# schematic.net
KiCad netlist of a schematic drawn in EAGLE
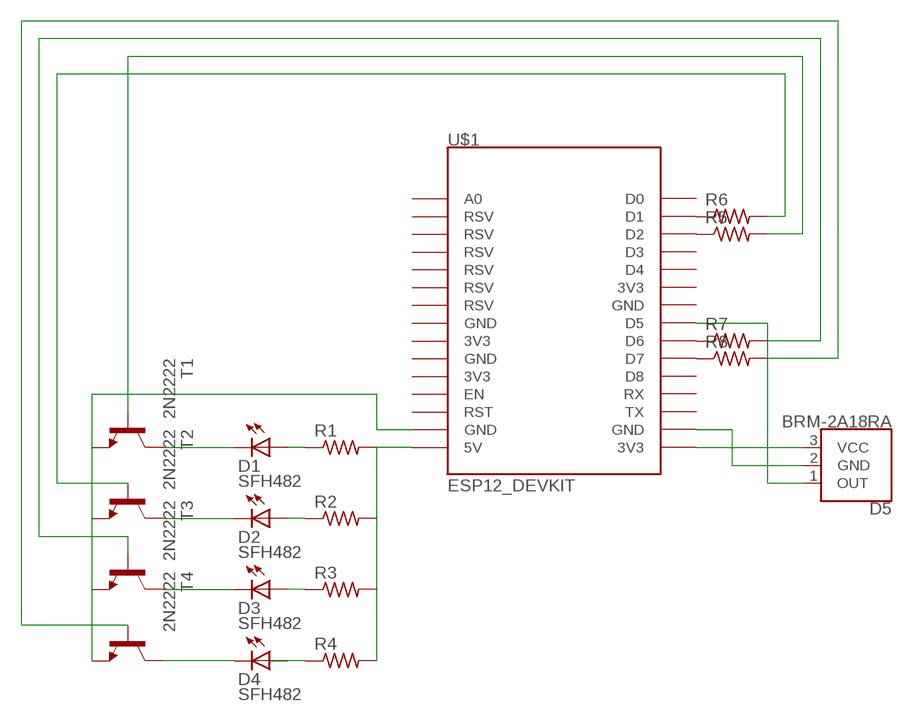
[diagram p0: schematic, sheet 1]

(export (version "E")
  (design (tool "Eeschema 10.0.6"))
  (components
    (comp (ref "D1")
      (value "SFH482")
      (footprint "eagle-import:SFH482")
      (libsource (lib "eagle-import") (part "SFH482"))
    )
    (comp (ref "D2")
      (value "SFH482")
      (footprint "eagle-import:SFH482")
      (libsource (lib "eagle-import") (part "SFH482"))
    )
    (comp (ref "D3")
      (value "SFH482")
      (footprint "eagle-import:SFH482")
      (libsource (lib "eagle-import") (part "SFH482"))
    )
    (comp (ref "D4")
      (value "SFH482")
      (footprint "eagle-import:SFH482")
      (libsource (lib "eagle-import") (part "SFH482"))
    )
    (comp (ref "D5")
      (value "BRM-2A18RA")
      (footprint "eagle-import:BRM-2508")
      (libsource (lib "eagle-import") (part "BRM-2A18RA"))
    )
    (comp (ref "R1")
      (value "R-US_0207/10")
      (footprint "eagle-import:0207_10")
      (libsource (lib "eagle-import") (part "R-US_0207/10"))
    )
    (comp (ref "R2")
      (value "R-US_0207/10")
      (footprint "eagle-import:0207_10")
      (libsource (lib "eagle-import") (part "R-US_0207/10"))
    )
    (comp (ref "R3")
      (value "R-US_0207/10")
      (footprint "eagle-import:0207_10")
      (libsource (lib "eagle-import") (part "R-US_0207/10"))
    )
    (comp (ref "R4")
      (value "R-US_0207/10")
      (footprint "eagle-import:0207_10")
      (libsource (lib "eagle-import") (part "R-US_0207/10"))
    )
    (comp (ref "R5")
      (value "R-US_0207/10")
      (footprint "eagle-import:0207_10")
      (libsource (lib "eagle-import") (part "R-US_0207/10"))
    )
    (comp (ref "R6")
      (value "R-US_0207/10")
      (footprint "eagle-import:0207_10")
      (libsource (lib "eagle-import") (part "R-US_0207/10"))
    )
    (comp (ref "R7")
      (value "R-US_0207/10")
      (footprint "eagle-import:0207_10")
      (libsource (lib "eagle-import") (part "R-US_0207/10"))
    )
    (comp (ref "R8")
      (value "R-US_0207/10")
      (footprint "eagle-import:0207_10")
      (libsource (lib "eagle-import") (part "R-US_0207/10"))
    )
    (comp (ref "T1")
      (value "2N2222")
      (footprint "eagle-import:TO18")
      (libsource (lib "eagle-import") (part "2N2222"))
    )
    (comp (ref "T2")
      (value "2N2222")
      (footprint "eagle-import:TO18")
      (libsource (lib "eagle-import") (part "2N2222"))
    )
    (comp (ref "T3")
      (value "2N2222")
      (footprint "eagle-import:TO18")
      (libsource (lib "eagle-import") (part "2N2222"))
    )
    (comp (ref "T4")
      (value "2N2222")
      (footprint "eagle-import:TO18")
      (libsource (lib "eagle-import") (part "2N2222"))
    )
    (comp (ref "U$1")
      (value "ESP12_DEVKIT")
      (footprint "eagle-import:ESP12_DEVKIT")
      (libsource (lib "eagle-import") (part "ESP12_DEVKIT"))
    )
  )
  (nets
    (net (code "1") (name "Net-(D1-C)") (class "Default")
      (node (ref "D1") (pin "K") (pinfunction "C_K") (pintype "passive"))
      (node (ref "T1") (pin "3") (pinfunction "C_3") (pintype "passive"))
    )
    (net (code "2") (name "Net-(D1-PadA)") (class "Default")
      (node (ref "D1") (pin "A") (pinfunction "A_A") (pintype "passive"))
      (node (ref "R1") (pin "1") (pinfunction "1_1") (pintype "passive"))
    )
    (net (code "3") (name "Net-(D2-C)") (class "Default")
      (node (ref "D2") (pin "K") (pinfunction "C_K") (pintype "passive"))
      (node (ref "T2") (pin "3") (pinfunction "C_3") (pintype "passive"))
    )
    (net (code "4") (name "Net-(D2-PadA)") (class "Default")
      (node (ref "D2") (pin "A") (pinfunction "A_A") (pintype "passive"))
      (node (ref "R2") (pin "1") (pinfunction "1_1") (pintype "passive"))
    )
    (net (code "5") (name "Net-(D3-C)") (class "Default")
      (node (ref "D3") (pin "K") (pinfunction "C_K") (pintype "passive"))
      (node (ref "T3") (pin "3") (pinfunction "C_3") (pintype "passive"))
    )
    (net (code "6") (name "Net-(D3-PadA)") (class "Default")
      (node (ref "D3") (pin "A") (pinfunction "A_A") (pintype "passive"))
      (node (ref "R3") (pin "1") (pinfunction "1_1") (pintype "passive"))
    )
    (net (code "7") (name "Net-(D4-C)") (class "Default")
      (node (ref "D4") (pin "K") (pinfunction "C_K") (pintype "passive"))
      (node (ref "T4") (pin "3") (pinfunction "C_3") (pintype "passive"))
    )
    (net (code "8") (name "Net-(D4-PadA)") (class "Default")
      (node (ref "D4") (pin "A") (pinfunction "A_A") (pintype "passive"))
      (node (ref "R4") (pin "1") (pinfunction "1_1") (pintype "passive"))
    )
    (net (code "9") (name "Net-(D5-GND)") (class "Default")
      (node (ref "D5") (pin "2") (pinfunction "GND_2") (pintype "bidirectional"))
      (node (ref "U$1") (pin "GND@3") (pinfunction "GND_GND@3") (pintype "bidirectional"))
    )
    (net (code "10") (name "Net-(D5-OUT)") (class "Default")
      (node (ref "D5") (pin "1") (pinfunction "OUT_1") (pintype "bidirectional"))
      (node (ref "U$1") (pin "D5") (pinfunction "D5_D5") (pintype "bidirectional"))
    )
    (net (code "11") (name "Net-(D5-VCC)") (class "Default")
      (node (ref "D5") (pin "3") (pinfunction "VCC_3") (pintype "bidirectional"))
      (node (ref "U$1") (pin "3V3@2") (pinfunction "3V3_3V3@2") (pintype "bidirectional"))
    )
    (net (code "12") (name "Net-(R1-Pad2)") (class "Default")
      (node (ref "R1") (pin "2") (pinfunction "2_2") (pintype "passive"))
      (node (ref "R2") (pin "2") (pinfunction "2_2") (pintype "passive"))
      (node (ref "R3") (pin "2") (pinfunction "2_2") (pintype "passive"))
      (node (ref "R4") (pin "2") (pinfunction "2_2") (pintype "passive"))
      (node (ref "U$1") (pin "5V") (pinfunction "5V_5V") (pintype "bidirectional"))
    )
    (net (code "13") (name "Net-(R5-Pad1)") (class "Default")
      (node (ref "R5") (pin "1") (pinfunction "1_1") (pintype "passive"))
      (node (ref "U$1") (pin "D2") (pinfunction "D2_D2") (pintype "bidirectional"))
    )
    (net (code "14") (name "Net-(R6-Pad1)") (class "Default")
      (node (ref "R6") (pin "1") (pinfunction "1_1") (pintype "passive"))
      (node (ref "U$1") (pin "D1") (pinfunction "D1_D1") (pintype "bidirectional"))
    )
    (net (code "15") (name "Net-(R7-Pad1)") (class "Default")
      (node (ref "R7") (pin "1") (pinfunction "1_1") (pintype "passive"))
      (node (ref "U$1") (pin "D6") (pinfunction "D6_D6") (pintype "bidirectional"))
    )
    (net (code "16") (name "Net-(R8-Pad1)") (class "Default")
      (node (ref "R8") (pin "1") (pinfunction "1_1") (pintype "passive"))
      (node (ref "U$1") (pin "D7") (pinfunction "D7_D7") (pintype "bidirectional"))
    )
    (net (code "17") (name "Net-(T1-B)") (class "Default")
      (node (ref "R5") (pin "2") (pinfunction "2_2") (pintype "passive"))
      (node (ref "T1") (pin "2") (pinfunction "B_2") (pintype "passive"))
    )
    (net (code "18") (name "Net-(T1-E)") (class "Default")
      (node (ref "T1") (pin "1") (pinfunction "E_1") (pintype "passive"))
      (node (ref "T2") (pin "1") (pinfunction "E_1") (pintype "passive"))
      (node (ref "T3") (pin "1") (pinfunction "E_1") (pintype "passive"))
      (node (ref "T4") (pin "1") (pinfunction "E_1") (pintype "passive"))
      (node (ref "U$1") (pin "GND@1") (pinfunction "GND_GND@1") (pintype "bidirectional"))
    )
    (net (code "19") (name "Net-(T2-B)") (class "Default")
      (node (ref "R6") (pin "2") (pinfunction "2_2") (pintype "passive"))
      (node (ref "T2") (pin "2") (pinfunction "B_2") (pintype "passive"))
    )
    (net (code "20") (name "Net-(T3-B)") (class "Default")
      (node (ref "R7") (pin "2") (pinfunction "2_2") (pintype "passive"))
      (node (ref "T3") (pin "2") (pinfunction "B_2") (pintype "passive"))
    )
    (net (code "21") (name "Net-(T4-B)") (class "Default")
      (node (ref "R8") (pin "2") (pinfunction "2_2") (pintype "passive"))
      (node (ref "T4") (pin "2") (pinfunction "B_2") (pintype "passive"))
    )
    (net (code "22") (name "unconnected-(U$1-3V3-Pad3V3@0)") (class "Default")
      (node (ref "U$1") (pin "3V3@0") (pinfunction "3V3_3V3@0") (pintype "bidirectional"))
    )
    (net (code "23") (name "unconnected-(U$1-3V3-Pad3V3@1)") (class "Default")
      (node (ref "U$1") (pin "3V3@1") (pinfunction "3V3_3V3@1") (pintype "bidirectional"))
    )
    (net (code "24") (name "unconnected-(U$1-3V3-Pad3V3@3)") (class "Default")
      (node (ref "U$1") (pin "3V3@3") (pinfunction "3V3_3V3@3") (pintype "bidirectional"))
    )
    (net (code "25") (name "unconnected-(U$1-GND-PadGND@0)") (class "Default")
      (node (ref "U$1") (pin "GND@0") (pinfunction "GND_GND@0") (pintype "bidirectional"))
    )
    (net (code "26") (name "unconnected-(U$1-GND-PadGND@2)") (class "Default")
      (node (ref "U$1") (pin "GND@2") (pinfunction "GND_GND@2") (pintype "bidirectional"))
    )
    (net (code "27") (name "unconnected-(U$1-GND-PadGND@4)") (class "Default")
      (node (ref "U$1") (pin "GND@4") (pinfunction "GND_GND@4") (pintype "bidirectional"))
    )
    (net (code "28") (name "unconnected-(U$1-PadA0)") (class "Default")
      (node (ref "U$1") (pin "A0") (pinfunction "A0_A0") (pintype "bidirectional"))
    )
    (net (code "29") (name "unconnected-(U$1-PadD0)") (class "Default")
      (node (ref "U$1") (pin "D0") (pinfunction "D0_D0") (pintype "bidirectional"))
    )
    (net (code "30") (name "unconnected-(U$1-PadD3)") (class "Default")
      (node (ref "U$1") (pin "D3") (pinfunction "D3_D3") (pintype "bidirectional"))
    )
    (net (code "31") (name "unconnected-(U$1-PadD4)") (class "Default")
      (node (ref "U$1") (pin "D4") (pinfunction "D4_D4") (pintype "bidirectional"))
    )
    (net (code "32") (name "unconnected-(U$1-PadD8)") (class "Default")
      (node (ref "U$1") (pin "D8") (pinfunction "D8_D8") (pintype "bidirectional"))
    )
    (net (code "33") (name "unconnected-(U$1-PadEN)") (class "Default")
      (node (ref "U$1") (pin "EN") (pinfunction "EN_EN") (pintype "bidirectional"))
    )
    (net (code "34") (name "unconnected-(U$1-PadRST)") (class "Default")
      (node (ref "U$1") (pin "RST") (pinfunction "RST_RST") (pintype "bidirectional"))
    )
    (net (code "35") (name "unconnected-(U$1-PadRX)") (class "Default")
      (node (ref "U$1") (pin "RX") (pinfunction "RX_RX") (pintype "bidirectional"))
    )
    (net (code "36") (name "unconnected-(U$1-PadTX)") (class "Default")
      (node (ref "U$1") (pin "TX") (pinfunction "TX_TX") (pintype "bidirectional"))
    )
    (net (code "37") (name "unconnected-(U$1-RSV-PadRSV@0)") (class "Default")
      (node (ref "U$1") (pin "RSV@0") (pinfunction "RSV_RSV@0") (pintype "bidirectional"))
    )
    (net (code "38") (name "unconnected-(U$1-RSV-PadRSV@1)") (class "Default")
      (node (ref "U$1") (pin "RSV@1") (pinfunction "RSV_RSV@1") (pintype "bidirectional"))
    )
    (net (code "39") (name "unconnected-(U$1-RSV-PadRSV@2)") (class "Default")
      (node (ref "U$1") (pin "RSV@2") (pinfunction "RSV_RSV@2") (pintype "bidirectional"))
    )
    (net (code "40") (name "unconnected-(U$1-RSV-PadRSV@3)") (class "Default")
      (node (ref "U$1") (pin "RSV@3") (pinfunction "RSV_RSV@3") (pintype "bidirectional"))
    )
    (net (code "41") (name "unconnected-(U$1-RSV-PadRSV@4)") (class "Default")
      (node (ref "U$1") (pin "RSV@4") (pinfunction "RSV_RSV@4") (pintype "bidirectional"))
    )
    (net (code "42") (name "unconnected-(U$1-RSV-PadRSV@5)") (class "Default")
      (node (ref "U$1") (pin "RSV@5") (pinfunction "RSV_RSV@5") (pintype "bidirectional"))
    )
  )
)
